# TMP006.net
KiCad netlist of a schematic drawn in EAGLE
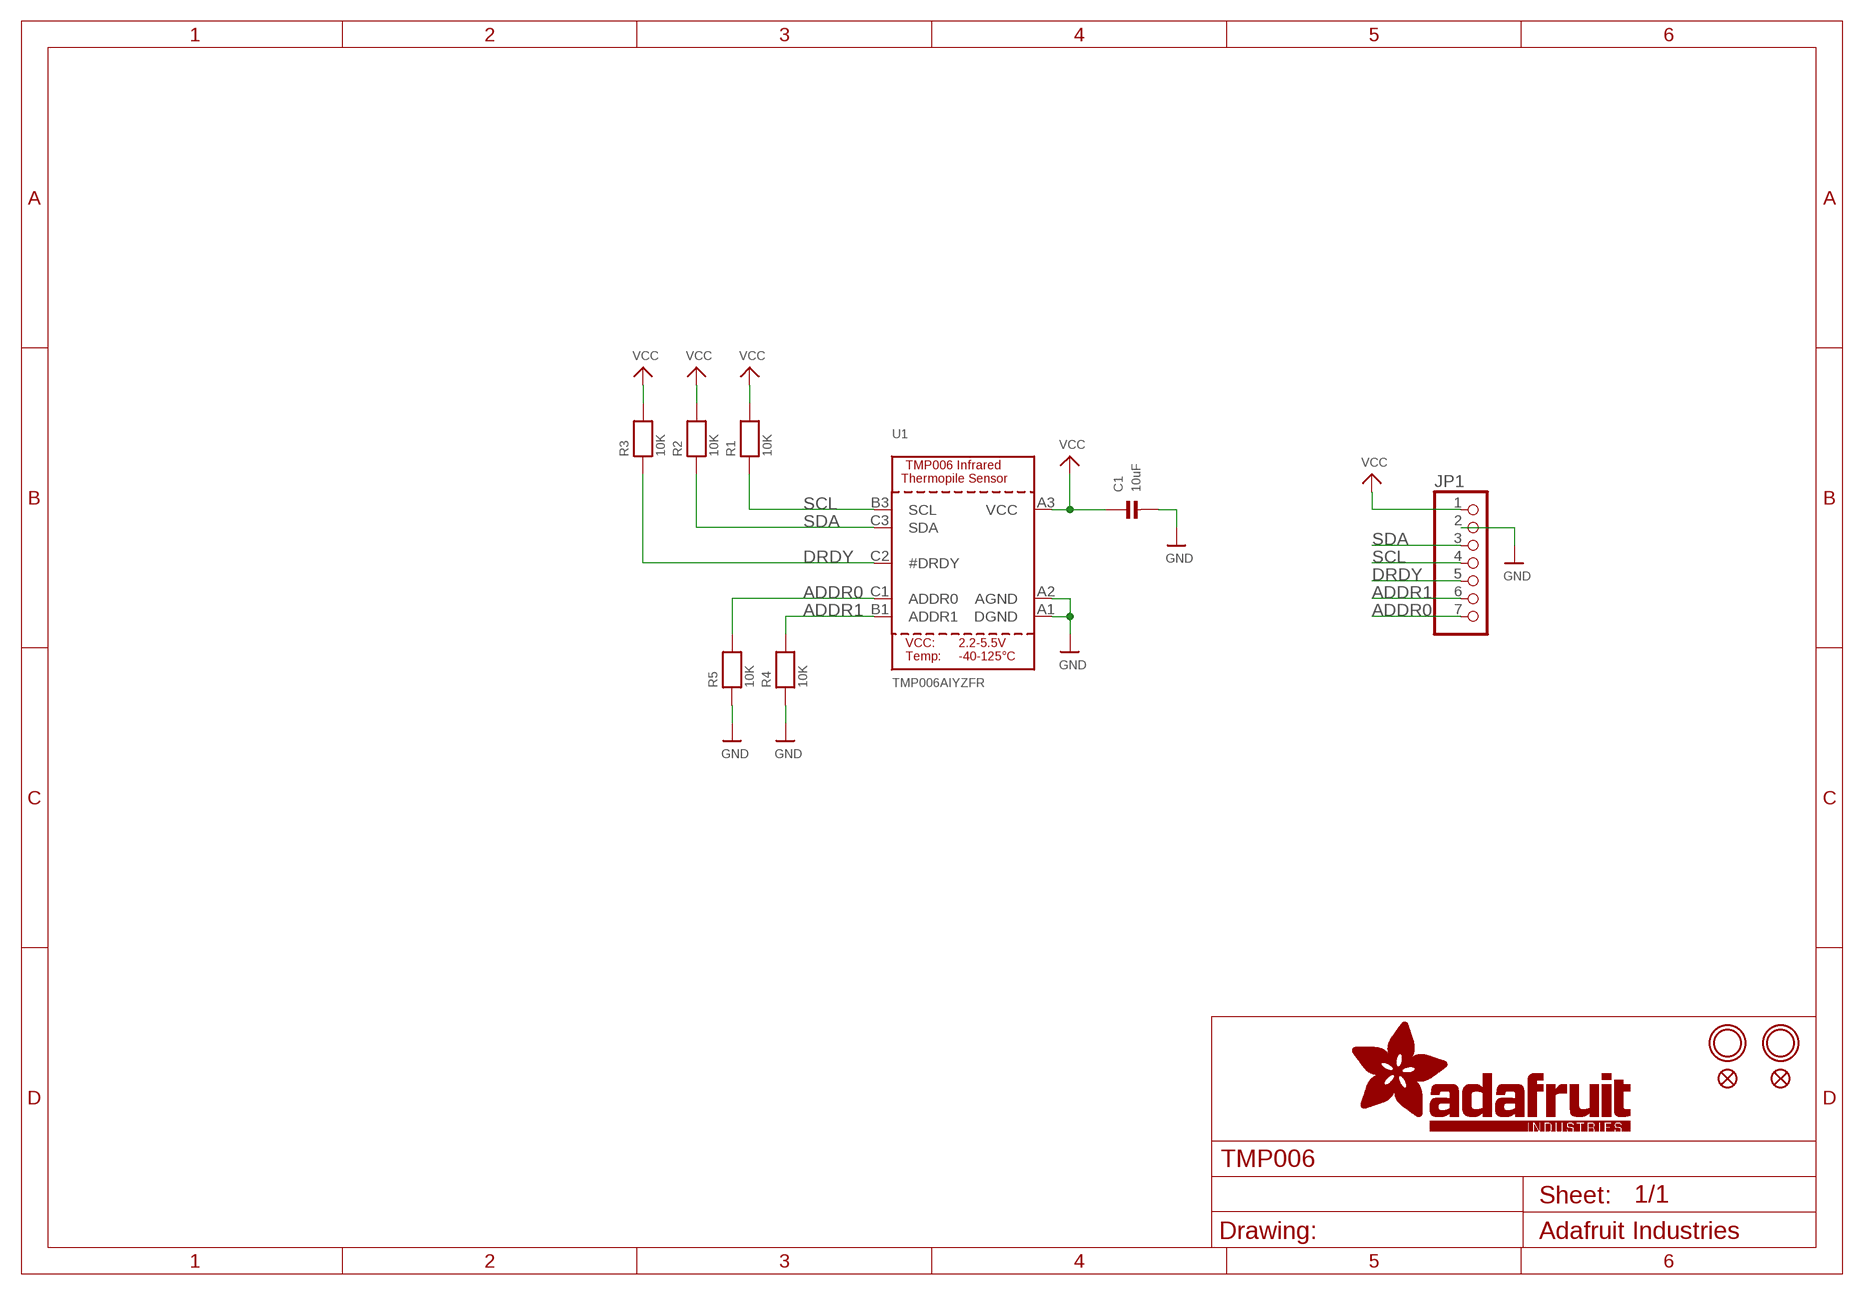
[diagram p0: schematic, sheet 1]

(export (version "E")
  (design (tool "Eeschema 10.0.6"))
  (components
    (comp (ref "C1")
      (value "10uF")
      (footprint "eagle-import:0805")
      (libsource (lib "eagle-import") (part "CAP_CERAMIC0805"))
    )
    (comp (ref "FID1")
      (value "FIDUCIAL\"\"")
      (footprint "eagle-import:FIDUCIAL_1MM")
      (libsource (lib "eagle-import") (part "FIDUCIAL{dblquote}{dblquote}"))
    )
    (comp (ref "FID2")
      (value "FIDUCIAL\"\"")
      (footprint "eagle-import:FIDUCIAL_1MM")
      (libsource (lib "eagle-import") (part "FIDUCIAL{dblquote}{dblquote}"))
    )
    (comp (ref "JP1")
      (value "HEADER-1X7THICKER")
      (footprint "eagle-import:1X07_ROUND_76")
      (libsource (lib "eagle-import") (part "HEADER-1X7THICKER"))
    )
    (comp (ref "R1")
      (value "10K")
      (footprint "eagle-import:0805")
      (libsource (lib "eagle-import") (part "RESISTOR0805"))
    )
    (comp (ref "R2")
      (value "10K")
      (footprint "eagle-import:0805")
      (libsource (lib "eagle-import") (part "RESISTOR0805"))
    )
    (comp (ref "R3")
      (value "10K")
      (footprint "eagle-import:0805")
      (libsource (lib "eagle-import") (part "RESISTOR0805"))
    )
    (comp (ref "R4")
      (value "10K")
      (footprint "eagle-import:0805")
      (libsource (lib "eagle-import") (part "RESISTOR0805"))
    )
    (comp (ref "R5")
      (value "10K")
      (footprint "eagle-import:0805")
      (libsource (lib "eagle-import") (part "RESISTOR0805"))
    )
    (comp (ref "U$6")
      (value "MOUNTINGHOLE2.5")
      (footprint "eagle-import:MOUNTINGHOLE_2.5_PLATED")
      (libsource (lib "eagle-import") (part "MOUNTINGHOLE2.5"))
    )
    (comp (ref "U$7")
      (value "MOUNTINGHOLE2.5")
      (footprint "eagle-import:MOUNTINGHOLE_2.5_PLATED")
      (libsource (lib "eagle-import") (part "MOUNTINGHOLE2.5"))
    )
    (comp (ref "U1")
      (value "TMP006AIYZFR")
      (footprint "eagle-import:WCSP-8")
      (libsource (lib "eagle-import") (part "TMP006"))
    )
  )
  (nets
    (net (code "1") (name "/ADDR0") (class "Default")
      (node (ref "JP1") (pin "7") (pinfunction "7_7") (pintype "passive"))
      (node (ref "R5") (pin "2") (pinfunction "2_2") (pintype "passive"))
      (node (ref "U1") (pin "C1") (pinfunction "ADDR0_C1") (pintype "input"))
    )
    (net (code "2") (name "/ADDR1") (class "Default")
      (node (ref "JP1") (pin "6") (pinfunction "6_6") (pintype "passive"))
      (node (ref "R4") (pin "2") (pinfunction "2_2") (pintype "passive"))
      (node (ref "U1") (pin "B1") (pinfunction "ADDR1_B1") (pintype "input"))
    )
    (net (code "3") (name "/DRDY") (class "Default")
      (node (ref "JP1") (pin "5") (pinfunction "5_5") (pintype "passive"))
      (node (ref "R3") (pin "1") (pinfunction "1_1") (pintype "passive"))
      (node (ref "U1") (pin "C2") (pinfunction "#DRDY_C2") (pintype "output"))
    )
    (net (code "4") (name "/SCL") (class "Default")
      (node (ref "JP1") (pin "4") (pinfunction "4_4") (pintype "passive"))
      (node (ref "R1") (pin "1") (pinfunction "1_1") (pintype "passive"))
      (node (ref "U1") (pin "B3") (pinfunction "SCL_B3") (pintype "input"))
    )
    (net (code "5") (name "/SDA") (class "Default")
      (node (ref "JP1") (pin "3") (pinfunction "3_3") (pintype "passive"))
      (node (ref "R2") (pin "1") (pinfunction "1_1") (pintype "passive"))
      (node (ref "U1") (pin "C3") (pinfunction "SDA_C3") (pintype "bidirectional"))
    )
    (net (code "6") (name "GND") (class "Default")
      (node (ref "C1") (pin "2") (pinfunction "P$2_2") (pintype "passive"))
      (node (ref "JP1") (pin "2") (pinfunction "2_2") (pintype "passive"))
      (node (ref "R4") (pin "1") (pinfunction "1_1") (pintype "passive"))
      (node (ref "R5") (pin "1") (pinfunction "1_1") (pintype "passive"))
      (node (ref "U1") (pin "A1") (pinfunction "DGND_A1") (pintype "power_in"))
      (node (ref "U1") (pin "A2") (pinfunction "AGND_A2") (pintype "power_in"))
    )
    (net (code "7") (name "VCC") (class "Default")
      (node (ref "C1") (pin "1") (pinfunction "P$1_1") (pintype "passive"))
      (node (ref "JP1") (pin "1") (pinfunction "1_1") (pintype "passive"))
      (node (ref "R1") (pin "2") (pinfunction "2_2") (pintype "passive"))
      (node (ref "R2") (pin "2") (pinfunction "2_2") (pintype "passive"))
      (node (ref "R3") (pin "2") (pinfunction "2_2") (pintype "passive"))
      (node (ref "U1") (pin "A3") (pinfunction "VCC_A3") (pintype "power_in"))
    )
  )
)
